# Voltage_measurement.net
KiCad netlist of a schematic drawn in Altium Designer
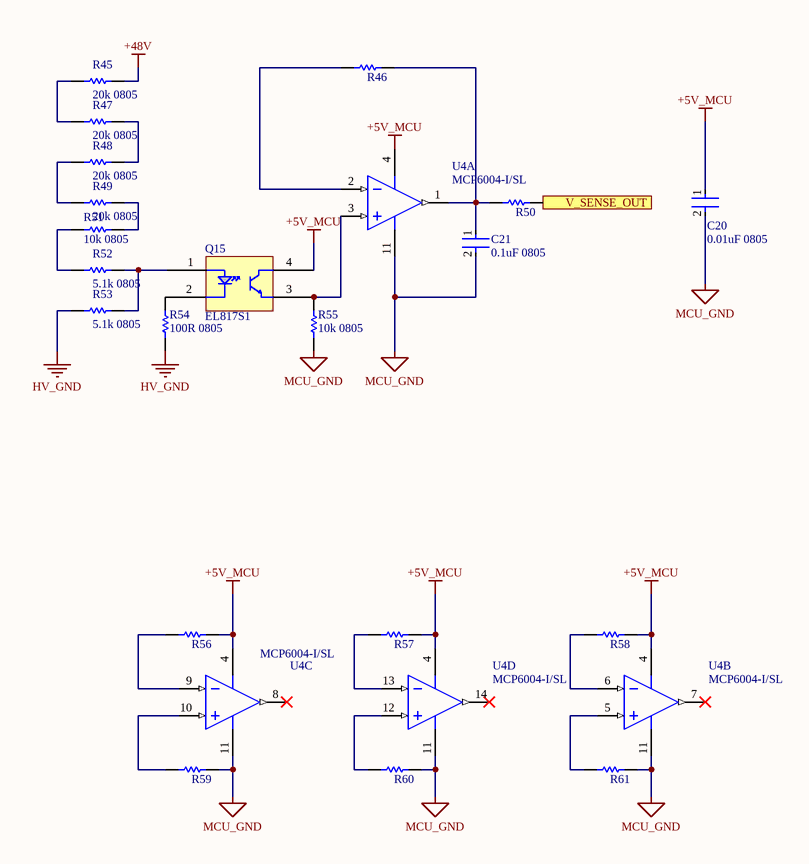
[diagram p0: Voltage_measurement.SchDoc]

(export (version "E")
  (design (tool "Eeschema 10.0.6"))
  (components
    (comp (ref "C20")
      (value "0.01uF 0805")
      (footprint "R0805")
      (description "10nF/0.01uF 50V Capacitor ±10% Tolerance 0805B103K500CT – 0805 Package")
      (libsource (lib "1kW_BLDC_Controller") (part "0.01uF 0805"))
    )
    (comp (ref "C21")
      (value "0.1uF 0805")
      (footprint "R0805")
      (description "0.1uF/100nF 100V Capacitor ±10% Tolerance CC0805KKX7R0BB104 – 0805 Package")
      (libsource (lib "1kW_BLDC_Controller") (part "0.1uF 0805"))
    )
    (comp (ref "Q15")
      (value "EL817S1")
      (footprint "EL817S1")
      (description "EL817S1 (B) (TU) – F Optocoupler SMD-4 Cut Tape")
      (libsource (lib "1kW_BLDC_Controller") (part "EL817S1"))
    )
    (comp (ref "R45")
      (value "20k 0805")
      (footprint "R0805")
      (description "20K ohm 1/8 Watt SMD Resistor 1% Tolerance RC0805FR-0720KL – 0805 Package")
      (libsource (lib "1kW_BLDC_Controller") (part "R0805"))
    )
    (comp (ref "R46")
      (value "0R 0603")
      (footprint "R0603")
      (description "0 Ohm 1/10 Watt Resistor 1% Tolerance RC0603FR-070RL – 0603 Package")
      (libsource (lib "1kW_BLDC_Controller") (part "R0000 0603"))
    )
    (comp (ref "R47")
      (value "20k 0805")
      (footprint "R0805")
      (description "20K ohm 1/8 Watt SMD Resistor 1% Tolerance RC0805FR-0720KL – 0805 Package")
      (libsource (lib "1kW_BLDC_Controller") (part "R0805"))
    )
    (comp (ref "R48")
      (value "20k 0805")
      (footprint "R0805")
      (description "20K ohm 1/8 Watt SMD Resistor 1% Tolerance RC0805FR-0720KL – 0805 Package")
      (libsource (lib "1kW_BLDC_Controller") (part "R0805"))
    )
    (comp (ref "R49")
      (value "20k 0805")
      (footprint "R0805")
      (description "20K ohm 1/8 Watt SMD Resistor 1% Tolerance RC0805FR-0720KL – 0805 Package")
      (libsource (lib "1kW_BLDC_Controller") (part "R0805"))
    )
    (comp (ref "R50")
      (value "0R 0603")
      (footprint "R0603")
      (description "0 Ohm 1/10 Watt Resistor 1% Tolerance RC0603FR-070RL – 0603 Package")
      (libsource (lib "1kW_BLDC_Controller") (part "R0000 0603"))
    )
    (comp (ref "R51")
      (value "10k 0805")
      (footprint "R0805")
      (description "10K Ohm 1/8 Watt Resistor 1% Tolerance RC0805FR-0710KL – 0805 Package")
      (libsource (lib "1kW_BLDC_Controller") (part "10k 0805"))
    )
    (comp (ref "R52")
      (value "5.1k 0805")
      (footprint "R0805")
      (description "5.1K Ohm 1/8 Watt Resistor 1% Tolerance 0805S8F5101T5E – 0805 Package")
      (libsource (lib "1kW_BLDC_Controller") (part "R0805"))
    )
    (comp (ref "R53")
      (value "5.1k 0805")
      (footprint "R0805")
      (description "5.1K Ohm 1/8 Watt Resistor 1% Tolerance 0805S8F5101T5E – 0805 Package")
      (libsource (lib "1kW_BLDC_Controller") (part "R0805"))
    )
    (comp (ref "R54")
      (value "100R 0805")
      (footprint "R0805")
      (description "100 ohm 1/4W Resistor 0805 Package")
      (libsource (lib "1kW_BLDC_Controller") (part "100R 0805"))
    )
    (comp (ref "R55")
      (value "10k 0805")
      (footprint "R0805")
      (description "10K Ohm 1/8 Watt Resistor 1% Tolerance RC0805FR-0710KL – 0805 Package")
      (libsource (lib "1kW_BLDC_Controller") (part "10k 0805"))
    )
    (comp (ref "R56")
      (value "0R 0603")
      (footprint "R0603")
      (description "0 Ohm 1/10 Watt Resistor 1% Tolerance RC0603FR-070RL – 0603 Package")
      (libsource (lib "1kW_BLDC_Controller") (part "R0000 0603"))
    )
    (comp (ref "R57")
      (value "0R 0603")
      (footprint "R0603")
      (description "0 Ohm 1/10 Watt Resistor 1% Tolerance RC0603FR-070RL – 0603 Package")
      (libsource (lib "1kW_BLDC_Controller") (part "R0000 0603"))
    )
    (comp (ref "R58")
      (value "0R 0603")
      (footprint "R0603")
      (description "0 Ohm 1/10 Watt Resistor 1% Tolerance RC0603FR-070RL – 0603 Package")
      (libsource (lib "1kW_BLDC_Controller") (part "R0000 0603"))
    )
    (comp (ref "R59")
      (value "0R 0603")
      (footprint "R0603")
      (description "0 Ohm 1/10 Watt Resistor 1% Tolerance RC0603FR-070RL – 0603 Package")
      (libsource (lib "1kW_BLDC_Controller") (part "R0000 0603"))
    )
    (comp (ref "R60")
      (value "0R 0603")
      (footprint "R0603")
      (description "0 Ohm 1/10 Watt Resistor 1% Tolerance RC0603FR-070RL – 0603 Package")
      (libsource (lib "1kW_BLDC_Controller") (part "R0000 0603"))
    )
    (comp (ref "R61")
      (value "0R 0603")
      (footprint "R0603")
      (description "0 Ohm 1/10 Watt Resistor 1% Tolerance RC0603FR-070RL – 0603 Package")
      (libsource (lib "1kW_BLDC_Controller") (part "R0000 0603"))
    )
    (comp (ref "U4")
      (value "MCP6004-I/SL")
      (footprint "SOIC-SL14_M")
      (description "MCP6004 1MHz Rail-to-Rail Operational Amplifier – SOIC-14 Package")
      (libsource (lib "Altium Content Vault") (part "AMP-OPA-MCP6004-IL14"))
    )
  )
  (nets
    (net (code "1") (name "+5V_MCU") (class "Default")
      (node (ref "C20") (pin "1") (pinfunction "1_1") (pintype "passive"))
      (node (ref "Q15") (pin "4") (pinfunction "C_4") (pintype "passive"))
      (node (ref "R56") (pin "1") (pinfunction "1_1") (pintype "passive"))
      (node (ref "R57") (pin "1") (pinfunction "1_1") (pintype "passive"))
      (node (ref "R58") (pin "1") (pinfunction "1_1") (pintype "passive"))
      (node (ref "U4") (pin "4") (pinfunction "VDD_4") (pintype "power_in"))
    )
    (net (code "2") (name "+48V") (class "Default")
      (node (ref "R45") (pin "2") (pinfunction "2_2") (pintype "passive"))
    )
    (net (code "3") (name "/V_SENSE_OUT") (class "Default")
      (node (ref "R50") (pin "1") (pinfunction "1_1") (pintype "passive"))
    )
    (net (code "4") (name "HV_GND") (class "Default")
      (node (ref "R53") (pin "1") (pinfunction "1_1") (pintype "passive"))
      (node (ref "R54") (pin "1") (pinfunction "1_1") (pintype "passive"))
    )
    (net (code "5") (name "MCU_GND") (class "Default")
      (node (ref "C20") (pin "2") (pinfunction "2_2") (pintype "passive"))
      (node (ref "C21") (pin "2") (pinfunction "2_2") (pintype "passive"))
      (node (ref "R55") (pin "1") (pinfunction "1_1") (pintype "passive"))
      (node (ref "R59") (pin "1") (pinfunction "1_1") (pintype "passive"))
      (node (ref "R60") (pin "1") (pinfunction "1_1") (pintype "passive"))
      (node (ref "R61") (pin "1") (pinfunction "1_1") (pintype "passive"))
      (node (ref "U4") (pin "11") (pinfunction "VSS_11") (pintype "power_in"))
    )
    (net (code "6") (name "Net-(Q15-A)") (class "Default")
      (node (ref "Q15") (pin "1") (pinfunction "A_1") (pintype "passive"))
      (node (ref "R52") (pin "2") (pinfunction "2_2") (pintype "passive"))
      (node (ref "R53") (pin "2") (pinfunction "2_2") (pintype "passive"))
    )
    (net (code "7") (name "Net-(Q15-E)") (class "Default")
      (node (ref "Q15") (pin "3") (pinfunction "E_3") (pintype "passive"))
      (node (ref "R55") (pin "2") (pinfunction "2_2") (pintype "passive"))
      (node (ref "U4") (pin "3") (pinfunction "VINA+_3") (pintype "input"))
    )
    (net (code "8") (name "Net-(Q15-K)") (class "Default")
      (node (ref "Q15") (pin "2") (pinfunction "K_2") (pintype "passive"))
      (node (ref "R54") (pin "2") (pinfunction "2_2") (pintype "passive"))
    )
    (net (code "9") (name "Net-(R45-Pad1)") (class "Default")
      (node (ref "R45") (pin "1") (pinfunction "1_1") (pintype "passive"))
      (node (ref "R47") (pin "1") (pinfunction "1_1") (pintype "passive"))
    )
    (net (code "10") (name "Net-(R47-Pad2)") (class "Default")
      (node (ref "R47") (pin "2") (pinfunction "2_2") (pintype "passive"))
      (node (ref "R48") (pin "2") (pinfunction "2_2") (pintype "passive"))
    )
    (net (code "11") (name "Net-(R48-Pad1)") (class "Default")
      (node (ref "R48") (pin "1") (pinfunction "1_1") (pintype "passive"))
      (node (ref "R49") (pin "1") (pinfunction "1_1") (pintype "passive"))
    )
    (net (code "12") (name "Net-(R49-Pad2)") (class "Default")
      (node (ref "R49") (pin "2") (pinfunction "2_2") (pintype "passive"))
      (node (ref "R51") (pin "1") (pinfunction "1_1") (pintype "passive"))
    )
    (net (code "13") (name "Net-(R51-Pad2)") (class "Default")
      (node (ref "R51") (pin "2") (pinfunction "2_2") (pintype "passive"))
      (node (ref "R52") (pin "1") (pinfunction "1_1") (pintype "passive"))
    )
    (net (code "14") (name "Net-(U4A-VINA-)") (class "Default")
      (node (ref "R46") (pin "2") (pinfunction "2_2") (pintype "passive"))
      (node (ref "U4") (pin "2") (pinfunction "VINA-_2") (pintype "input"))
    )
    (net (code "15") (name "Net-(U4A-VOUTA)") (class "Default")
      (node (ref "C21") (pin "1") (pinfunction "1_1") (pintype "passive"))
      (node (ref "R46") (pin "1") (pinfunction "1_1") (pintype "passive"))
      (node (ref "R50") (pin "2") (pinfunction "2_2") (pintype "passive"))
      (node (ref "U4") (pin "1") (pinfunction "VOUTA_1") (pintype "output"))
    )
    (net (code "16") (name "Net-(U4B-VINB+)") (class "Default")
      (node (ref "R61") (pin "2") (pinfunction "2_2") (pintype "passive"))
      (node (ref "U4") (pin "5") (pinfunction "VINB+_5") (pintype "input"))
    )
    (net (code "17") (name "Net-(U4B-VINB-)") (class "Default")
      (node (ref "R58") (pin "2") (pinfunction "2_2") (pintype "passive"))
      (node (ref "U4") (pin "6") (pinfunction "VINB-_6") (pintype "input"))
    )
    (net (code "18") (name "Net-(U4C-VINC+)") (class "Default")
      (node (ref "R59") (pin "2") (pinfunction "2_2") (pintype "passive"))
      (node (ref "U4") (pin "10") (pinfunction "VINC+_10") (pintype "input"))
    )
    (net (code "19") (name "Net-(U4C-VINC-)") (class "Default")
      (node (ref "R56") (pin "2") (pinfunction "2_2") (pintype "passive"))
      (node (ref "U4") (pin "9") (pinfunction "VINC-_9") (pintype "input"))
    )
    (net (code "20") (name "Net-(U4D-VIND+)") (class "Default")
      (node (ref "R60") (pin "2") (pinfunction "2_2") (pintype "passive"))
      (node (ref "U4") (pin "12") (pinfunction "VIND+_12") (pintype "input"))
    )
    (net (code "21") (name "Net-(U4D-VIND-)") (class "Default")
      (node (ref "R57") (pin "2") (pinfunction "2_2") (pintype "passive"))
      (node (ref "U4") (pin "13") (pinfunction "VIND-_13") (pintype "input"))
    )
    (net (code "22") (name "unconnected-(U4B-VOUTB-Pad7)") (class "Default")
      (node (ref "U4") (pin "7") (pinfunction "VOUTB_7") (pintype "output+no_connect"))
    )
    (net (code "23") (name "unconnected-(U4C-VOUTC-Pad8)") (class "Default")
      (node (ref "U4") (pin "8") (pinfunction "VOUTC_8") (pintype "output+no_connect"))
    )
    (net (code "24") (name "unconnected-(U4D-VOUTD-Pad14)") (class "Default")
      (node (ref "U4") (pin "14") (pinfunction "VOUTD_14") (pintype "output+no_connect"))
    )
  )
)
